# Digit_Board_add.net
KiCad netlist of a schematic drawn in Altium Designer
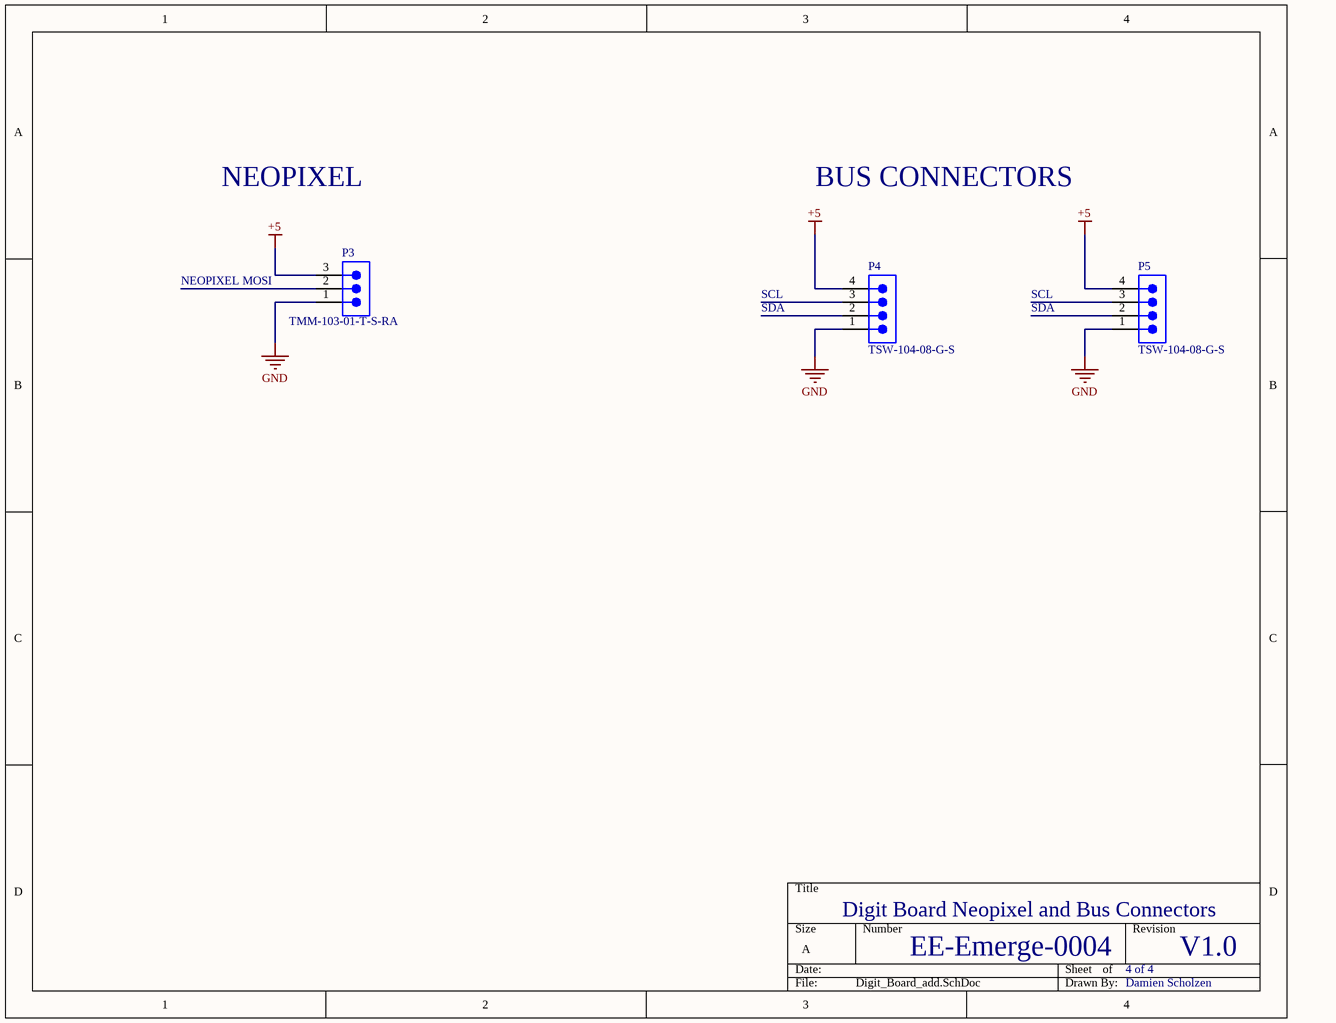
[diagram p0: Digit_Board_add.SchDoc]

(export (version "E")
  (design (tool "Eeschema 10.0.6"))
  (components
    (comp (ref "P3")
      (value "TMM-103-01-T-S-RA")
      (footprint "SMTC-TMM-103-01-X-S-RA")
      (description "Low Profile Through-Hole Header, Right Angle, -55 to 105 degC, 2 mm Pitch, 3-Pin, Male, RoHS")
      (fields (field (name "MANUFACTURER") "Samtec"))
      (libsource (lib "EE_Emerge_SkillsProject (1)") (part "CMP-1029-00176-1"))
    )
    (comp (ref "P4")
      (value "TSW-104-08-G-S")
      (footprint "SMTC-TSW-104-08-X-S")
      (description "0.025\" SQ Post Header, Through-hole, Vertical, -55 to 125 degC, 2.54 mm Pitch, 4-Pin, Male, RoHS")
      (fields (field (name "MANUFACTURER") "Samtec"))
      (libsource (lib "Altium Content Vault") (part "SMTC-TSW-104-08-X-S"))
    )
    (comp (ref "P5")
      (value "TSW-104-08-G-S")
      (footprint "SMTC-TSW-104-08-X-S")
      (description "0.025\" SQ Post Header, Through-hole, Vertical, -55 to 125 degC, 2.54 mm Pitch, 4-Pin, Male, RoHS")
      (fields (field (name "MANUFACTURER") "Samtec"))
      (libsource (lib "Altium Content Vault") (part "SMTC-TSW-104-08-X-S"))
    )
  )
  (nets
    (net (code "1") (name "+5") (class "Default")
      (node (ref "P3") (pin "3") (pinfunction "3_3") (pintype "passive"))
      (node (ref "P4") (pin "4") (pinfunction "4_4") (pintype "passive"))
      (node (ref "P5") (pin "4") (pinfunction "4_4") (pintype "passive"))
    )
    (net (code "2") (name "GND") (class "Default")
      (node (ref "P3") (pin "1") (pinfunction "1_1") (pintype "passive"))
      (node (ref "P4") (pin "1") (pinfunction "1_1") (pintype "passive"))
      (node (ref "P5") (pin "1") (pinfunction "1_1") (pintype "passive"))
    )
    (net (code "3") (name "unconnected-(P3-Pad2)") (class "Default")
      (node (ref "P3") (pin "2") (pinfunction "2_2") (pintype "passive"))
    )
    (net (code "4") (name "unconnected-(P4-Pad2)") (class "Default")
      (node (ref "P4") (pin "2") (pinfunction "2_2") (pintype "passive"))
    )
    (net (code "5") (name "unconnected-(P4-Pad3)") (class "Default")
      (node (ref "P4") (pin "3") (pinfunction "3_3") (pintype "passive"))
    )
    (net (code "6") (name "unconnected-(P5-Pad2)") (class "Default")
      (node (ref "P5") (pin "2") (pinfunction "2_2") (pintype "passive"))
    )
    (net (code "7") (name "unconnected-(P5-Pad3)") (class "Default")
      (node (ref "P5") (pin "3") (pinfunction "3_3") (pintype "passive"))
    )
  )
)
